# UWB___Sensor_Extension_Board.net
KiCad netlist of a schematic drawn in EasyEDA Pro
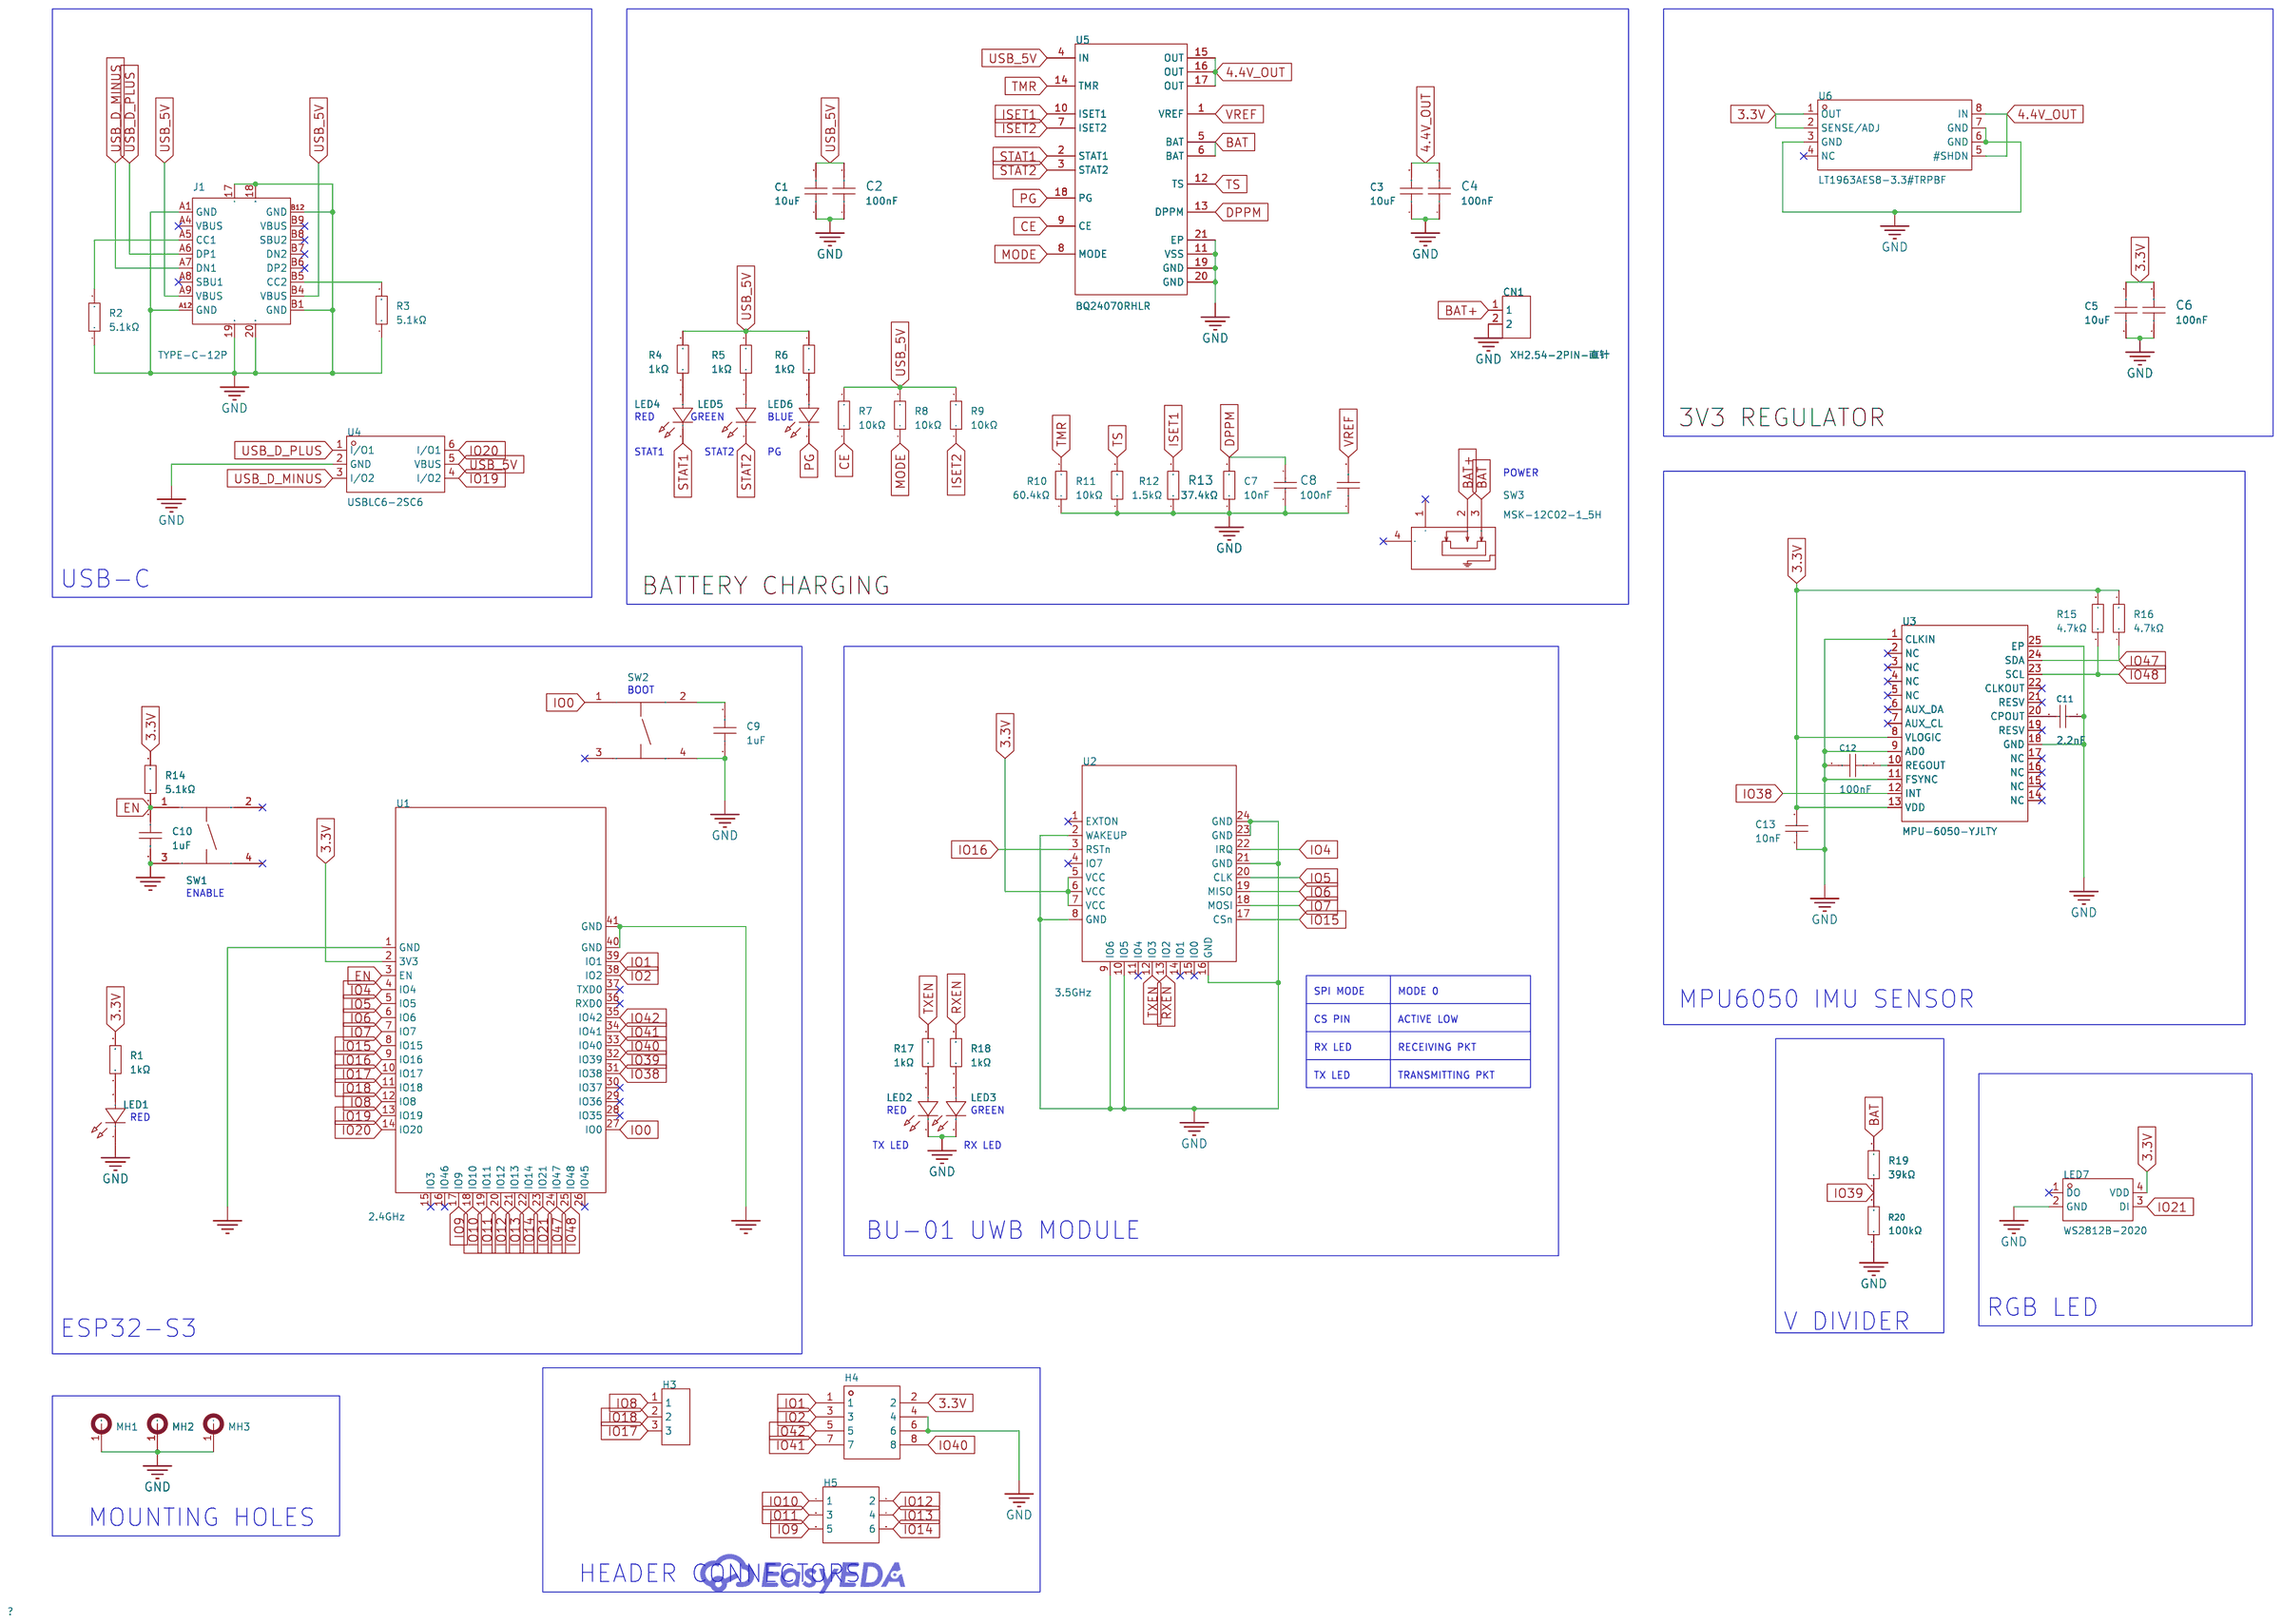
[diagram p0: schematic sheet]

(export (version "E")
  (design (tool "Eeschema 10.0.6"))
  (components
    (comp (ref "C1")
      (value "10uF")
      (footprint "easyedapro:C0603")
      (description "Capacitance:10uF Tolerance:±10% Tolerance:±10% Voltage Rating:10V Temperature Coefficient:X5R")
      (fields
        (field (name "Manufacturer Part") "CL10A106KP8NNNC")
        (field (name "Manufacturer") "SAMSUNG(三星)")
      )
      (libsource (lib "easyedapro") (part "CL10A106KP8NNNC"))
    )
    (comp (ref "C2")
      (value "100nF")
      (footprint "easyedapro:C0603")
      (description "Capacitance:100nF Tolerance:±10% Tolerance:±10% Voltage Rating:10V Temperature Coefficient:X7R")
      (fields
        (field (name "Manufacturer Part") "CC0603KRX7R6BB104")
        (field (name "Manufacturer") "YAGEO(国巨)")
      )
      (libsource (lib "easyedapro") (part "CC0603KRX7R6BB104"))
    )
    (comp (ref "C3")
      (value "10uF")
      (footprint "easyedapro:C0603")
      (description "Capacitance:10uF Tolerance:±10% Tolerance:±10% Voltage Rating:10V Temperature Coefficient:X5R")
      (fields
        (field (name "Manufacturer Part") "CL10A106KP8NNNC")
        (field (name "Manufacturer") "SAMSUNG(三星)")
      )
      (libsource (lib "easyedapro") (part "CL10A106KP8NNNC"))
    )
    (comp (ref "C4")
      (value "100nF")
      (footprint "easyedapro:C0603")
      (description "Capacitance:100nF Tolerance:±10% Tolerance:±10% Voltage Rating:10V Temperature Coefficient:X7R")
      (fields
        (field (name "Manufacturer Part") "CC0603KRX7R6BB104")
        (field (name "Manufacturer") "YAGEO(国巨)")
      )
      (libsource (lib "easyedapro") (part "CC0603KRX7R6BB104"))
    )
    (comp (ref "C5")
      (value "10uF")
      (footprint "easyedapro:C0603")
      (description "Capacitance:10uF Tolerance:±10% Tolerance:±10% Voltage Rating:10V Temperature Coefficient:X5R")
      (fields
        (field (name "Manufacturer Part") "CL10A106KP8NNNC")
        (field (name "Manufacturer") "SAMSUNG(三星)")
      )
      (libsource (lib "easyedapro") (part "CL10A106KP8NNNC"))
    )
    (comp (ref "C6")
      (value "100nF")
      (footprint "easyedapro:C0603")
      (description "Capacitance:100nF Tolerance:±10% Tolerance:±10% Voltage Rating:10V Temperature Coefficient:X7R")
      (fields
        (field (name "Manufacturer Part") "CC0603KRX7R6BB104")
        (field (name "Manufacturer") "YAGEO(国巨)")
      )
      (libsource (lib "easyedapro") (part "CC0603KRX7R6BB104"))
    )
    (comp (ref "C7")
      (value "10nF")
      (footprint "easyedapro:C0603")
      (description "Capacitance:10nF Tolerance:±5% Tolerance:±5% Voltage Rating:50V Temperature Coefficient:X7R")
      (fields
        (field (name "Manufacturer Part") "CC0603JRX7R9BB103")
        (field (name "Manufacturer") "YAGEO(国巨)")
      )
      (libsource (lib "easyedapro") (part "CC0603JRX7R9BB103"))
    )
    (comp (ref "C8")
      (value "100nF")
      (footprint "easyedapro:C0603")
      (description "Capacitance:100nF Tolerance:±10% Tolerance:±10% Voltage Rating:10V Temperature Coefficient:X7R")
      (fields
        (field (name "Manufacturer Part") "CC0603KRX7R6BB104")
        (field (name "Manufacturer") "YAGEO(国巨)")
      )
      (libsource (lib "easyedapro") (part "CC0603KRX7R6BB104"))
    )
    (comp (ref "C9")
      (value "1uF")
      (footprint "easyedapro:C0603")
      (fields (field (name "Manufacturer Part") "0603X105K250CT") (field (name "Manufacturer") "Walsin(华新科)"))
      (libsource (lib "easyedapro") (part "0603X105K250CT"))
    )
    (comp (ref "C10")
      (value "1uF")
      (footprint "easyedapro:C0603")
      (fields (field (name "Manufacturer Part") "0603X105K250CT") (field (name "Manufacturer") "Walsin(华新科)"))
      (libsource (lib "easyedapro") (part "0603X105K250CT"))
    )
    (comp (ref "C11")
      (value "2.2nF")
      (footprint "easyedapro:C0603")
      (description "Capacitance:2.2nF Tolerance:±5% Tolerance:±5% Voltage Rating:50V Temperature Coefficient:NP0")
      (fields
        (field (name "Manufacturer Part") "CC0603JRNPO9BN222")
        (field (name "Manufacturer") "YAGEO(国巨)")
      )
      (libsource (lib "easyedapro") (part "CC0603JRNPO9BN222"))
    )
    (comp (ref "C12")
      (value "100nF")
      (footprint "easyedapro:C0603")
      (description "Capacitance:100nF Tolerance:±10% Tolerance:±10% Voltage Rating:10V Temperature Coefficient:X7R")
      (fields
        (field (name "Manufacturer Part") "CC0603KRX7R6BB104")
        (field (name "Manufacturer") "YAGEO(国巨)")
      )
      (libsource (lib "easyedapro") (part "CC0603KRX7R6BB104"))
    )
    (comp (ref "C13")
      (value "10nF")
      (footprint "easyedapro:C0603")
      (description "Capacitance:10nF Tolerance:±5% Tolerance:±5% Voltage Rating:50V Temperature Coefficient:X7R")
      (fields
        (field (name "Manufacturer Part") "CC0603JRX7R9BB103")
        (field (name "Manufacturer") "YAGEO(国巨)")
      )
      (libsource (lib "easyedapro") (part "CC0603JRX7R9BB103"))
    )
    (comp (ref "CN1")
      (value "XH2.54-2PIN-直针")
      (footprint "easyedapro:CONN-TH_XH2.54-2P")
      (libsource (lib "easyedapro") (part "XH2.54-2PIN-直针"))
    )
    (comp (ref "H3")
      (value "~")
      (footprint "easyedapro:HDR-TH_3P-P2.54-V-M")
      (libsource (lib "easyedapro") (part "PZ254V-11-03P_C2937625"))
    )
    (comp (ref "H4")
      (value "~")
      (footprint "easyedapro:HDR-TH_8P-P2.54-V-M-R2-C4-S2.54")
      (libsource (lib "easyedapro") (part "HDR-M-2.54_2x4"))
    )
    (comp (ref "H5")
      (value "~")
      (footprint "easyedapro:HDR-TH_6P-P2.54-V-R2-C3-S2.54_A2541WV-2X3P")
      (libsource (lib "easyedapro") (part "HDR-M-2.54_2x3"))
    )
    (comp (ref "J1")
      (value "TYPE-C-12P")
      (footprint "easyedapro:USB-SMD_TYPE-C16PIN")
      (libsource (lib "easyedapro") (part "TYPE-C-12P"))
    )
    (comp (ref "LED1")
      (value "19-217/GHC-YR1S2/6T")
      (footprint "easyedapro:LED0603-RD_GREEN")
      (fields (field (name "Manufacturer") "EVERLIGHT(亿光)"))
      (libsource (lib "easyedapro") (part "19-217/GHC-YR1S2/6T"))
    )
    (comp (ref "LED2")
      (value "19-217/GHC-YR1S2/6T")
      (footprint "easyedapro:LED0603-RD_GREEN")
      (fields (field (name "Manufacturer") "EVERLIGHT(亿光)"))
      (libsource (lib "easyedapro") (part "19-217/GHC-YR1S2/6T"))
    )
    (comp (ref "LED3")
      (value "19-217/GHC-YR1S2/6T")
      (footprint "easyedapro:LED0603-RD_GREEN")
      (fields (field (name "Manufacturer") "EVERLIGHT(亿光)"))
      (libsource (lib "easyedapro") (part "19-217/GHC-YR1S2/6T"))
    )
    (comp (ref "LED4")
      (value "19-217/GHC-YR1S2/6T")
      (footprint "easyedapro:LED0603-RD_GREEN")
      (fields (field (name "Manufacturer") "EVERLIGHT(亿光)"))
      (libsource (lib "easyedapro") (part "19-217/GHC-YR1S2/6T"))
    )
    (comp (ref "LED5")
      (value "19-217/GHC-YR1S2/6T")
      (footprint "easyedapro:LED0603-RD_GREEN")
      (fields (field (name "Manufacturer") "EVERLIGHT(亿光)"))
      (libsource (lib "easyedapro") (part "19-217/GHC-YR1S2/6T"))
    )
    (comp (ref "LED6")
      (value "19-217/GHC-YR1S2/6T")
      (footprint "easyedapro:LED0603-RD_GREEN")
      (fields (field (name "Manufacturer") "EVERLIGHT(亿光)"))
      (libsource (lib "easyedapro") (part "19-217/GHC-YR1S2/6T"))
    )
    (comp (ref "LED7")
      (value "WS2812B-2020")
      (footprint "easyedapro:LED-SMD_4P-L2.0-W2.0-TL_WS2812B-2020")
      (fields (field (name "Manufacturer") "worldsemi"))
      (libsource (lib "easyedapro") (part "WS2812B-2020"))
    )
    (comp (ref "MH1")
      (value "~")
      (footprint "easyedapro:MH_7.5x2.7mm")
      (libsource (lib "easyedapro") (part "MH_7.5x2.7mm"))
    )
    (comp (ref "MH2")
      (value "~")
      (footprint "easyedapro:MH_7.5x2.7mm")
      (libsource (lib "easyedapro") (part "MH_7.5x2.7mm"))
    )
    (comp (ref "MH3")
      (value "~")
      (footprint "easyedapro:MH_7.5x2.7mm")
      (libsource (lib "easyedapro") (part "MH_7.5x2.7mm"))
    )
    (comp (ref "R1")
      (value "1kΩ")
      (footprint "easyedapro:R0603")
      (fields (field (name "Manufacturer Part") "RC0603FR-071KL") (field (name "Manufacturer") "YAGEO(国巨)"))
      (libsource (lib "easyedapro") (part "RC0603FR-071KL"))
    )
    (comp (ref "R2")
      (value "5.1kΩ")
      (footprint "easyedapro:R0603")
      (fields (field (name "Manufacturer Part") "RC0603FR-075K1L") (field (name "Manufacturer") "YAGEO(国巨)"))
      (libsource (lib "easyedapro") (part "RC0603FR-075K1L"))
    )
    (comp (ref "R3")
      (value "5.1kΩ")
      (footprint "easyedapro:R0603")
      (fields (field (name "Manufacturer Part") "RC0603FR-075K1L") (field (name "Manufacturer") "YAGEO(国巨)"))
      (libsource (lib "easyedapro") (part "RC0603FR-075K1L"))
    )
    (comp (ref "R4")
      (value "1kΩ")
      (footprint "easyedapro:R0603")
      (fields (field (name "Manufacturer Part") "RC0603FR-071KL") (field (name "Manufacturer") "YAGEO(国巨)"))
      (libsource (lib "easyedapro") (part "RC0603FR-071KL"))
    )
    (comp (ref "R5")
      (value "1kΩ")
      (footprint "easyedapro:R0603")
      (fields (field (name "Manufacturer Part") "RC0603FR-071KL") (field (name "Manufacturer") "YAGEO(国巨)"))
      (libsource (lib "easyedapro") (part "RC0603FR-071KL"))
    )
    (comp (ref "R6")
      (value "1kΩ")
      (footprint "easyedapro:R0603")
      (fields (field (name "Manufacturer Part") "RC0603FR-071KL") (field (name "Manufacturer") "YAGEO(国巨)"))
      (libsource (lib "easyedapro") (part "RC0603FR-071KL"))
    )
    (comp (ref "R7")
      (value "10kΩ")
      (footprint "easyedapro:R0603")
      (fields (field (name "Manufacturer Part") "RC0603FR-0710KL") (field (name "Manufacturer") "YAGEO(国巨)"))
      (libsource (lib "easyedapro") (part "RC0603FR-0710KL"))
    )
    (comp (ref "R8")
      (value "10kΩ")
      (footprint "easyedapro:R0603")
      (fields (field (name "Manufacturer Part") "RC0603FR-0710KL") (field (name "Manufacturer") "YAGEO(国巨)"))
      (libsource (lib "easyedapro") (part "RC0603FR-0710KL"))
    )
    (comp (ref "R9")
      (value "10kΩ")
      (footprint "easyedapro:R0603")
      (fields (field (name "Manufacturer Part") "RC0603FR-0710KL") (field (name "Manufacturer") "YAGEO(国巨)"))
      (libsource (lib "easyedapro") (part "RC0603FR-0710KL"))
    )
    (comp (ref "R10")
      (value "60.4kΩ")
      (footprint "easyedapro:R0603")
      (fields (field (name "Manufacturer Part") "RC0603FR-0760K4L") (field (name "Manufacturer") "YAGEO(国巨)"))
      (libsource (lib "easyedapro") (part "RC0603FR-0760K4L"))
    )
    (comp (ref "R11")
      (value "10kΩ")
      (footprint "easyedapro:R0603")
      (fields (field (name "Manufacturer Part") "RC0603FR-0710KL") (field (name "Manufacturer") "YAGEO(国巨)"))
      (libsource (lib "easyedapro") (part "RC0603FR-0710KL"))
    )
    (comp (ref "R12")
      (value "1.5kΩ")
      (footprint "easyedapro:R0603")
      (fields (field (name "Manufacturer Part") "RC0603FR-071K5L") (field (name "Manufacturer") "YAGEO(国巨)"))
      (libsource (lib "easyedapro") (part "RC0603FR-071K5L"))
    )
    (comp (ref "R13")
      (value "37.4kΩ")
      (footprint "easyedapro:R0603")
      (fields
        (field (name "Manufacturer Part") "0603WAF3742T5E")
        (field (name "Manufacturer") "UNI-ROYAL(厚声)")
      )
      (libsource (lib "easyedapro") (part "0603WAF3742T5E"))
    )
    (comp (ref "R14")
      (value "5.1kΩ")
      (footprint "easyedapro:R0603")
      (fields (field (name "Manufacturer Part") "RC0603FR-075K1L") (field (name "Manufacturer") "YAGEO(国巨)"))
      (libsource (lib "easyedapro") (part "RC0603FR-075K1L"))
    )
    (comp (ref "R15")
      (value "4.7kΩ")
      (footprint "easyedapro:R0603")
      (fields (field (name "Manufacturer Part") "RC0603FR-074K7L") (field (name "Manufacturer") "YAGEO(国巨)"))
      (libsource (lib "easyedapro") (part "RC0603FR-074K7L"))
    )
    (comp (ref "R16")
      (value "4.7kΩ")
      (footprint "easyedapro:R0603")
      (fields (field (name "Manufacturer Part") "RC0603FR-074K7L") (field (name "Manufacturer") "YAGEO(国巨)"))
      (libsource (lib "easyedapro") (part "RC0603FR-074K7L"))
    )
    (comp (ref "R17")
      (value "1kΩ")
      (footprint "easyedapro:R0603")
      (fields (field (name "Manufacturer Part") "RC0603FR-071KL") (field (name "Manufacturer") "YAGEO(国巨)"))
      (libsource (lib "easyedapro") (part "RC0603FR-071KL"))
    )
    (comp (ref "R18")
      (value "1kΩ")
      (footprint "easyedapro:R0603")
      (fields (field (name "Manufacturer Part") "RC0603FR-071KL") (field (name "Manufacturer") "YAGEO(国巨)"))
      (libsource (lib "easyedapro") (part "RC0603FR-071KL"))
    )
    (comp (ref "R19")
      (value "39kΩ")
      (footprint "easyedapro:R0603")
      (fields (field (name "Manufacturer Part") "RC0603FR-0739KL") (field (name "Manufacturer") "YAGEO(国巨)"))
      (libsource (lib "easyedapro") (part "RC0603FR-0739KL"))
    )
    (comp (ref "R20")
      (value "100kΩ")
      (footprint "easyedapro:R0603")
      (fields (field (name "Manufacturer Part") "RC0603FR-07100KL") (field (name "Manufacturer") "YAGEO(国巨)"))
      (libsource (lib "easyedapro") (part "RC0603FR-07100KL"))
    )
    (comp (ref "SW1")
      (value "TS3315A")
      (footprint "easyedapro:SW-SMD_4P-L3.4-W3.4-P2.00-LS4.0")
      (fields (field (name "Manufacturer") "SHOU HAN(首韩)"))
      (libsource (lib "easyedapro") (part "TS3315A"))
    )
    (comp (ref "SW2")
      (value "TS3315A")
      (footprint "easyedapro:SW-SMD_4P-L3.4-W3.4-P2.00-LS4.0")
      (fields (field (name "Manufacturer") "SHOU HAN(首韩)"))
      (libsource (lib "easyedapro") (part "TS3315A"))
    )
    (comp (ref "SW3")
      (value "MSK-12C02-1_5H")
      (footprint "easyedapro:SW-TH_MSK12C02")
      (libsource (lib "easyedapro") (part "MSK-12C02-1_5H"))
    )
    (comp (ref "U1")
      (value "2.4GHz")
      (footprint "easyedapro:WIRELM-SMD_ESP32-S3-WROOM-1")
      (fields
        (field (name "Manufacturer Part") "ESP32-S3-WROOM-1-N16R8")
        (field (name "Manufacturer") "ESPRESSIF(乐鑫)")
      )
      (libsource (lib "easyedapro") (part "ESP32-S3-WROOM-1(N16R8)"))
    )
    (comp (ref "U2")
      (value "3.5GHz")
      (footprint "easyedapro:COMM-SMD_BU01")
      (fields (field (name "Manufacturer Part") "BU01") (field (name "Manufacturer") "Ai-Thinker(安信可)"))
      (libsource (lib "easyedapro") (part "BU01"))
    )
    (comp (ref "U3")
      (value "MPU-6050-YJLTY")
      (footprint "easyedapro:QFN-24_L4.0-W4.0-P0.50-TL-EP2.7")
      (libsource (lib "easyedapro") (part "MPU-6050-YJLTY_C9900004367"))
    )
    (comp (ref "U4")
      (value "USBLC6-2SC6")
      (footprint "easyedapro:SOT-23-6_L2.9-W1.6-P0.95-LS2.8-BL")
      (description "Maximum Clamping Voltage:15V Breakdown Voltage:6V Number of Lines:双路 Type:ESD")
      (fields (field (name "Manufacturer") "UMW(友台半导体)"))
      (libsource (lib "easyedapro") (part "USBLC6-2SC6_C2687116"))
    )
    (comp (ref "U5")
      (value "BQ24070RHLR")
      (footprint "easyedapro:QFN-20_L4.7-W3.7-P0.50-BL-EP")
      (fields (field (name "Manufacturer") "TI(德州仪器)"))
      (libsource (lib "easyedapro") (part "BQ24070RHLR"))
    )
    (comp (ref "U6")
      (value "LT1963AES8-3.3#TRPBF")
      (footprint "easyedapro:SO-8_L4.9-W3.9-P1.27-LS5.9-BL")
      (description "Output Type:-")
      (libsource (lib "easyedapro") (part "LT1963AES8-3.3#TRPBF_C514417"))
    )
  )
  (nets
    (net (code "1") (name "3.3V") (class "Default")
      (node (ref "C13") (pin "2") (pinfunction "2_2") (pintype "input"))
      (node (ref "C5") (pin "2") (pinfunction "2_2") (pintype "unspecified"))
      (node (ref "C6") (pin "2") (pinfunction "2_2") (pintype "input"))
      (node (ref "H4") (pin "2") (pinfunction "2_2") (pintype "input"))
      (node (ref "LED7") (pin "4") (pinfunction "VDD_4") (pintype "unspecified"))
      (node (ref "R1") (pin "2") (pinfunction "2_2") (pintype "input"))
      (node (ref "R14") (pin "2") (pinfunction "2_2") (pintype "input"))
      (node (ref "R15") (pin "2") (pinfunction "2_2") (pintype "input"))
      (node (ref "R16") (pin "2") (pinfunction "2_2") (pintype "input"))
      (node (ref "U1") (pin "2") (pinfunction "3V3_2") (pintype "unspecified"))
      (node (ref "U2") (pin "5") (pinfunction "VCC_5") (pintype "unspecified"))
      (node (ref "U2") (pin "6") (pinfunction "VCC_6") (pintype "unspecified"))
      (node (ref "U2") (pin "7") (pinfunction "VCC_7") (pintype "unspecified"))
      (node (ref "U3") (pin "13") (pinfunction "VDD_13") (pintype "unspecified"))
      (node (ref "U3") (pin "8") (pinfunction "VLOGIC_8") (pintype "unspecified"))
      (node (ref "U6") (pin "1") (pinfunction "OUT_1") (pintype "unspecified"))
      (node (ref "U6") (pin "2") (pinfunction "SENSE/ADJ_2") (pintype "unspecified"))
    )
    (net (code "2") (name "4.4V_OUT") (class "Default")
      (node (ref "C3") (pin "2") (pinfunction "2_2") (pintype "unspecified"))
      (node (ref "C4") (pin "2") (pinfunction "2_2") (pintype "input"))
      (node (ref "U5") (pin "15") (pinfunction "OUT_15") (pintype "unspecified"))
      (node (ref "U5") (pin "16") (pinfunction "OUT_16") (pintype "unspecified"))
      (node (ref "U5") (pin "17") (pinfunction "OUT_17") (pintype "unspecified"))
      (node (ref "U6") (pin "5") (pinfunction "#SHDN_5") (pintype "unspecified"))
      (node (ref "U6") (pin "8") (pinfunction "IN_8") (pintype "unspecified"))
    )
    (net (code "3") (name "BAT") (class "Default")
      (node (ref "R19") (pin "2") (pinfunction "2_2") (pintype "unspecified"))
      (node (ref "SW3") (pin "3") (pinfunction "3_3") (pintype "unspecified"))
      (node (ref "U5") (pin "5") (pinfunction "BAT_5") (pintype "unspecified"))
      (node (ref "U5") (pin "6") (pinfunction "BAT_6") (pintype "unspecified"))
    )
    (net (code "4") (name "BAT+") (class "Default")
      (node (ref "CN1") (pin "1") (pinfunction "1_1") (pintype "unspecified"))
      (node (ref "SW3") (pin "2") (pinfunction "2_2") (pintype "unspecified"))
    )
    (net (code "5") (name "CE") (class "Default")
      (node (ref "R7") (pin "1") (pinfunction "1_1") (pintype "input"))
      (node (ref "U5") (pin "9") (pinfunction "CE_9") (pintype "unspecified"))
    )
    (net (code "6") (name "DPPM") (class "Default")
      (node (ref "C7") (pin "2") (pinfunction "2_2") (pintype "input"))
      (node (ref "R13") (pin "2") (pinfunction "2_2") (pintype "input"))
      (node (ref "U5") (pin "13") (pinfunction "DPPM_13") (pintype "unspecified"))
    )
    (net (code "7") (name "EN") (class "Default")
      (node (ref "C10") (pin "1") (pinfunction "1_1") (pintype "unspecified"))
      (node (ref "R14") (pin "1") (pinfunction "1_1") (pintype "input"))
      (node (ref "SW1") (pin "1") (pinfunction "A_1") (pintype "unspecified"))
      (node (ref "U1") (pin "3") (pinfunction "EN_3") (pintype "unspecified"))
    )
    (net (code "8") (name "GND") (class "Default")
      (node (ref "C1") (pin "1") (pinfunction "1_1") (pintype "unspecified"))
      (node (ref "C10") (pin "2") (pinfunction "2_2") (pintype "unspecified"))
      (node (ref "C11") (pin "2") (pinfunction "2_2") (pintype "input"))
      (node (ref "C12") (pin "2") (pinfunction "2_2") (pintype "input"))
      (node (ref "C13") (pin "1") (pinfunction "1_1") (pintype "input"))
      (node (ref "C2") (pin "1") (pinfunction "1_1") (pintype "input"))
      (node (ref "C3") (pin "1") (pinfunction "1_1") (pintype "unspecified"))
      (node (ref "C4") (pin "1") (pinfunction "1_1") (pintype "input"))
      (node (ref "C5") (pin "1") (pinfunction "1_1") (pintype "unspecified"))
      (node (ref "C6") (pin "1") (pinfunction "1_1") (pintype "input"))
      (node (ref "C7") (pin "1") (pinfunction "1_1") (pintype "input"))
      (node (ref "C8") (pin "1") (pinfunction "1_1") (pintype "input"))
      (node (ref "C9") (pin "2") (pinfunction "2_2") (pintype "unspecified"))
      (node (ref "CN1") (pin "2") (pinfunction "2_2") (pintype "unspecified"))
      (node (ref "H4") (pin "4") (pinfunction "4_4") (pintype "input"))
      (node (ref "H4") (pin "6") (pinfunction "6_6") (pintype "input"))
      (node (ref "J1") (pin "17") (pinfunction "17_17") (pintype "unspecified"))
      (node (ref "J1") (pin "18") (pinfunction "18_18") (pintype "unspecified"))
      (node (ref "J1") (pin "19") (pinfunction "19_19") (pintype "unspecified"))
      (node (ref "J1") (pin "20") (pinfunction "20_20") (pintype "unspecified"))
      (node (ref "J1") (pin "A1") (pinfunction "GND_A1") (pintype "unspecified"))
      (node (ref "J1") (pin "A12") (pinfunction "GND_A12") (pintype "unspecified"))
      (node (ref "J1") (pin "B1") (pinfunction "GND_B1") (pintype "unspecified"))
      (node (ref "J1") (pin "B12") (pinfunction "GND_B12") (pintype "unspecified"))
      (node (ref "LED1") (pin "1") (pinfunction "K_1") (pintype "unspecified"))
      (node (ref "LED2") (pin "1") (pinfunction "K_1") (pintype "unspecified"))
      (node (ref "LED3") (pin "1") (pinfunction "K_1") (pintype "unspecified"))
      (node (ref "LED7") (pin "2") (pinfunction "GND_2") (pintype "unspecified"))
      (node (ref "MH1") (pin "1") (pinfunction "1_1") (pintype "input"))
      (node (ref "MH2") (pin "1") (pinfunction "1_1") (pintype "input"))
      (node (ref "MH3") (pin "1") (pinfunction "1_1") (pintype "input"))
      (node (ref "R10") (pin "1") (pinfunction "1_1") (pintype "unspecified"))
      (node (ref "R11") (pin "1") (pinfunction "1_1") (pintype "input"))
      (node (ref "R12") (pin "1") (pinfunction "1_1") (pintype "input"))
      (node (ref "R13") (pin "1") (pinfunction "1_1") (pintype "input"))
      (node (ref "R2") (pin "1") (pinfunction "1_1") (pintype "input"))
      (node (ref "R20") (pin "1") (pinfunction "1_1") (pintype "input"))
      (node (ref "R3") (pin "1") (pinfunction "1_1") (pintype "input"))
      (node (ref "SW1") (pin "3") (pinfunction "C_3") (pintype "unspecified"))
      (node (ref "SW2") (pin "4") (pinfunction "D_4") (pintype "unspecified"))
      (node (ref "U1") (pin "1") (pinfunction "GND_1") (pintype "unspecified"))
      (node (ref "U1") (pin "40") (pinfunction "GND_40") (pintype "unspecified"))
      (node (ref "U1") (pin "41") (pinfunction "GND_41") (pintype "unspecified"))
      (node (ref "U2") (pin "10") (pinfunction "IO5_10") (pintype "unspecified"))
      (node (ref "U2") (pin "16") (pinfunction "GND_16") (pintype "unspecified"))
      (node (ref "U2") (pin "2") (pinfunction "WAKEUP_2") (pintype "unspecified"))
      (node (ref "U2") (pin "21") (pinfunction "GND_21") (pintype "unspecified"))
      (node (ref "U2") (pin "23") (pinfunction "GND_23") (pintype "unspecified"))
      (node (ref "U2") (pin "24") (pinfunction "GND_24") (pintype "unspecified"))
      (node (ref "U2") (pin "8") (pinfunction "GND_8") (pintype "unspecified"))
      (node (ref "U2") (pin "9") (pinfunction "IO6_9") (pintype "unspecified"))
      (node (ref "U3") (pin "1") (pinfunction "CLKIN_1") (pintype "unspecified"))
      (node (ref "U3") (pin "11") (pinfunction "FSYNC_11") (pintype "unspecified"))
      (node (ref "U3") (pin "18") (pinfunction "GND_18") (pintype "unspecified"))
      (node (ref "U3") (pin "25") (pinfunction "EP_25") (pintype "unspecified"))
      (node (ref "U3") (pin "9") (pinfunction "AD0_9") (pintype "unspecified"))
      (node (ref "U4") (pin "2") (pinfunction "GND_2") (pintype "unspecified"))
      (node (ref "U5") (pin "11") (pinfunction "VSS_11") (pintype "unspecified"))
      (node (ref "U5") (pin "19") (pinfunction "GND_19") (pintype "unspecified"))
      (node (ref "U5") (pin "20") (pinfunction "GND_20") (pintype "unspecified"))
      (node (ref "U5") (pin "21") (pinfunction "EP_21") (pintype "unspecified"))
      (node (ref "U6") (pin "3") (pinfunction "GND_3") (pintype "unspecified"))
      (node (ref "U6") (pin "6") (pinfunction "GND_6") (pintype "unspecified"))
      (node (ref "U6") (pin "7") (pinfunction "GND_7") (pintype "unspecified"))
    )
    (net (code "9") (name "IO0") (class "Default")
      (node (ref "SW2") (pin "1") (pinfunction "A_1") (pintype "unspecified"))
      (node (ref "U1") (pin "27") (pinfunction "IO0_27") (pintype "unspecified"))
    )
    (net (code "10") (name "IO1") (class "Default")
      (node (ref "H4") (pin "1") (pinfunction "1_1") (pintype "input"))
      (node (ref "U1") (pin "39") (pinfunction "IO1_39") (pintype "unspecified"))
    )
    (net (code "11") (name "IO2") (class "Default")
      (node (ref "H4") (pin "3") (pinfunction "3_3") (pintype "input"))
      (node (ref "U1") (pin "38") (pinfunction "IO2_38") (pintype "unspecified"))
    )
    (net (code "12") (name "IO4") (class "Default")
      (node (ref "U1") (pin "4") (pinfunction "IO4_4") (pintype "unspecified"))
      (node (ref "U2") (pin "22") (pinfunction "IRQ_22") (pintype "unspecified"))
    )
    (net (code "13") (name "IO5") (class "Default")
      (node (ref "U1") (pin "5") (pinfunction "IO5_5") (pintype "unspecified"))
      (node (ref "U2") (pin "20") (pinfunction "CLK_20") (pintype "unspecified"))
    )
    (net (code "14") (name "IO6") (class "Default")
      (node (ref "U1") (pin "6") (pinfunction "IO6_6") (pintype "unspecified"))
      (node (ref "U2") (pin "19") (pinfunction "MISO_19") (pintype "unspecified"))
    )
    (net (code "15") (name "IO7") (class "Default")
      (node (ref "U1") (pin "7") (pinfunction "IO7_7") (pintype "unspecified"))
      (node (ref "U2") (pin "18") (pinfunction "MOSI_18") (pintype "unspecified"))
    )
    (net (code "16") (name "IO8") (class "Default")
      (node (ref "H3") (pin "1") (pinfunction "1_1") (pintype "unspecified"))
      (node (ref "U1") (pin "12") (pinfunction "IO8_12") (pintype "unspecified"))
    )
    (net (code "17") (name "IO9") (class "Default")
      (node (ref "H5") (pin "5") (pinfunction "5_5") (pintype "input"))
      (node (ref "U1") (pin "17") (pinfunction "IO9_17") (pintype "unspecified"))
    )
    (net (code "18") (name "IO10") (class "Default")
      (node (ref "H5") (pin "1") (pinfunction "1_1") (pintype "input"))
      (node (ref "U1") (pin "18") (pinfunction "IO10_18") (pintype "unspecified"))
    )
    (net (code "19") (name "IO11") (class "Default")
      (node (ref "H5") (pin "3") (pinfunction "3_3") (pintype "input"))
      (node (ref "U1") (pin "19") (pinfunction "IO11_19") (pintype "unspecified"))
    )
    (net (code "20") (name "IO12") (class "Default")
      (node (ref "H5") (pin "2") (pinfunction "2_2") (pintype "input"))
      (node (ref "U1") (pin "20") (pinfunction "IO12_20") (pintype "unspecified"))
    )
    (net (code "21") (name "IO13") (class "Default")
      (node (ref "H5") (pin "4") (pinfunction "4_4") (pintype "input"))
      (node (ref "U1") (pin "21") (pinfunction "IO13_21") (pintype "unspecified"))
    )
    (net (code "22") (name "IO14") (class "Default")
      (node (ref "H5") (pin "6") (pinfunction "6_6") (pintype "input"))
      (node (ref "U1") (pin "22") (pinfunction "IO14_22") (pintype "unspecified"))
    )
    (net (code "23") (name "IO15") (class "Default")
      (node (ref "U1") (pin "8") (pinfunction "IO15_8") (pintype "unspecified"))
      (node (ref "U2") (pin "17") (pinfunction "CSn_17") (pintype "unspecified"))
    )
    (net (code "24") (name "IO16") (class "Default")
      (node (ref "U1") (pin "9") (pinfunction "IO16_9") (pintype "unspecified"))
      (node (ref "U2") (pin "3") (pinfunction "RSTn_3") (pintype "unspecified"))
    )
    (net (code "25") (name "IO17") (class "Default")
      (node (ref "H3") (pin "3") (pinfunction "3_3") (pintype "unspecified"))
      (node (ref "U1") (pin "10") (pinfunction "IO17_10") (pintype "unspecified"))
    )
    (net (code "26") (name "IO18") (class "Default")
      (node (ref "H3") (pin "2") (pinfunction "2_2") (pintype "unspecified"))
      (node (ref "U1") (pin "11") (pinfunction "IO18_11") (pintype "unspecified"))
    )
    (net (code "27") (name "IO19") (class "Default")
      (node (ref "U1") (pin "13") (pinfunction "IO19_13") (pintype "unspecified"))
      (node (ref "U4") (pin "4") (pinfunction "I/O2_4") (pintype "unspecified"))
    )
    (net (code "28") (name "IO20") (class "Default")
      (node (ref "U1") (pin "14") (pinfunction "IO20_14") (pintype "unspecified"))
      (node (ref "U4") (pin "6") (pinfunction "I/O1_6") (pintype "unspecified"))
    )
    (net (code "29") (name "IO21") (class "Default")
      (node (ref "LED7") (pin "3") (pinfunction "DI_3") (pintype "unspecified"))
      (node (ref "U1") (pin "23") (pinfunction "IO21_23") (pintype "unspecified"))
    )
    (net (code "30") (name "IO38") (class "Default")
      (node (ref "U1") (pin "31") (pinfunction "IO38_31") (pintype "unspecified"))
      (node (ref "U3") (pin "12") (pinfunction "INT_12") (pintype "unspecified"))
    )
    (net (code "31") (name "IO39") (class "Default")
      (node (ref "R19") (pin "1") (pinfunction "1_1") (pintype "unspecified"))
      (node (ref "R20") (pin "2") (pinfunction "2_2") (pintype "input"))
      (node (ref "U1") (pin "32") (pinfunction "IO39_32") (pintype "unspecified"))
    )
    (net (code "32") (name "IO40") (class "Default")
      (node (ref "H4") (pin "8") (pinfunction "8_8") (pintype "input"))
      (node (ref "U1") (pin "33") (pinfunction "IO40_33") (pintype "unspecified"))
    )
    (net (code "33") (name "IO41") (class "Default")
      (node (ref "H4") (pin "7") (pinfunction "7_7") (pintype "input"))
      (node (ref "U1") (pin "34") (pinfunction "IO41_34") (pintype "unspecified"))
    )
    (net (code "34") (name "IO42") (class "Default")
      (node (ref "H4") (pin "5") (pinfunction "5_5") (pintype "input"))
      (node (ref "U1") (pin "35") (pinfunction "IO42_35") (pintype "unspecified"))
    )
    (net (code "35") (name "IO47") (class "Default")
      (node (ref "R16") (pin "1") (pinfunction "1_1") (pintype "input"))
      (node (ref "U1") (pin "24") (pinfunction "IO47_24") (pintype "unspecified"))
      (node (ref "U3") (pin "24") (pinfunction "SDA_24") (pintype "unspecified"))
    )
    (net (code "36") (name "IO48") (class "Default")
      (node (ref "R15") (pin "1") (pinfunction "1_1") (pintype "input"))
      (node (ref "U1") (pin "25") (pinfunction "IO48_25") (pintype "unspecified"))
      (node (ref "U3") (pin "23") (pinfunction "SCL_23") (pintype "unspecified"))
    )
    (net (code "37") (name "ISET1") (class "Default")
      (node (ref "R12") (pin "2") (pinfunction "2_2") (pintype "input"))
      (node (ref "U5") (pin "10") (pinfunction "ISET1_10") (pintype "unspecified"))
    )
    (net (code "38") (name "ISET2") (class "Default")
      (node (ref "R9") (pin "1") (pinfunction "1_1") (pintype "input"))
      (node (ref "U5") (pin "7") (pinfunction "ISET2_7") (pintype "unspecified"))
    )
    (net (code "39") (name "MODE") (class "Default")
      (node (ref "R8") (pin "1") (pinfunction "1_1") (pintype "input"))
      (node (ref "U5") (pin "8") (pinfunction "MODE_8") (pintype "unspecified"))
    )
    (net (code "40") (name "Net-(J1-CC1)") (class "Default")
      (node (ref "J1") (pin "A5") (pinfunction "CC1_A5") (pintype "unspecified"))
      (node (ref "R2") (pin "2") (pinfunction "2_2") (pintype "input"))
    )
    (net (code "41") (name "Net-(J1-CC2)") (class "Default")
      (node (ref "J1") (pin "B5") (pinfunction "CC2_B5") (pintype "unspecified"))
      (node (ref "R3") (pin "2") (pinfunction "2_2") (pintype "input"))
    )
    (net (code "42") (name "Net-(LED1-A)") (class "Default")
      (node (ref "LED1") (pin "2") (pinfunction "A_2") (pintype "unspecified"))
      (node (ref "R1") (pin "1") (pinfunction "1_1") (pintype "input"))
    )
    (net (code "43") (name "Net-(LED2-A)") (class "Default")
      (node (ref "LED2") (pin "2") (pinfunction "A_2") (pintype "unspecified"))
      (node (ref "R17") (pin "1") (pinfunction "1_1") (pintype "input"))
    )
    (net (code "44") (name "Net-(LED3-A)") (class "Default")
      (node (ref "LED3") (pin "2") (pinfunction "A_2") (pintype "unspecified"))
      (node (ref "R18") (pin "1") (pinfunction "1_1") (pintype "input"))
    )
    (net (code "45") (name "Net-(LED4-A)") (class "Default")
      (node (ref "LED4") (pin "2") (pinfunction "A_2") (pintype "unspecified"))
      (node (ref "R4") (pin "1") (pinfunction "1_1") (pintype "input"))
    )
    (net (code "46") (name "Net-(LED5-A)") (class "Default")
      (node (ref "LED5") (pin "2") (pinfunction "A_2") (pintype "unspecified"))
      (node (ref "R5") (pin "1") (pinfunction "1_1") (pintype "input"))
    )
    (net (code "47") (name "Net-(LED6-A)") (class "Default")
      (node (ref "LED6") (pin "2") (pinfunction "A_2") (pintype "unspecified"))
      (node (ref "R6") (pin "1") (pinfunction "1_1") (pintype "input"))
    )
    (net (code "48") (name "Net-(SW2-B)") (class "Default")
      (node (ref "C9") (pin "1") (pinfunction "1_1") (pintype "unspecified"))
      (node (ref "SW2") (pin "2") (pinfunction "B_2") (pintype "unspecified"))
    )
    (net (code "49") (name "Net-(U3-CPOUT)") (class "Default")
      (node (ref "C11") (pin "1") (pinfunction "1_1") (pintype "input"))
      (node (ref "U3") (pin "20") (pinfunction "CPOUT_20") (pintype "unspecified"))
    )
    (net (code "50") (name "Net-(U3-REGOUT)") (class "Default")
      (node (ref "C12") (pin "1") (pinfunction "1_1") (pintype "input"))
      (node (ref "U3") (pin "10") (pinfunction "REGOUT_10") (pintype "unspecified"))
    )
    (net (code "51") (name "PG") (class "Default")
      (node (ref "LED6") (pin "1") (pinfunction "K_1") (pintype "unspecified"))
      (node (ref "U5") (pin "18") (pinfunction "PG_18") (pintype "unspecified"))
    )
    (net (code "52") (name "RXEN") (class "Default")
      (node (ref "R18") (pin "2") (pinfunction "2_2") (pintype "input"))
      (node (ref "U2") (pin "13") (pinfunction "IO2_13") (pintype "unspecified"))
    )
    (net (code "53") (name "STAT1") (class "Default")
      (node (ref "LED4") (pin "1") (pinfunction "K_1") (pintype "unspecified"))
      (node (ref "U5") (pin "2") (pinfunction "STAT1_2") (pintype "unspecified"))
    )
    (net (code "54") (name "STAT2") (class "Default")
      (node (ref "LED5") (pin "1") (pinfunction "K_1") (pintype "unspecified"))
      (node (ref "U5") (pin "3") (pinfunction "STAT2_3") (pintype "unspecified"))
    )
    (net (code "55") (name "TMR") (class "Default")
      (node (ref "R10") (pin "2") (pinfunction "2_2") (pintype "unspecified"))
      (node (ref "U5") (pin "14") (pinfunction "TMR_14") (pintype "unspecified"))
    )
    (net (code "56") (name "TS") (class "Default")
      (node (ref "R11") (pin "2") (pinfunction "2_2") (pintype "input"))
      (node (ref "U5") (pin "12") (pinfunction "TS_12") (pintype "unspecified"))
    )
    (net (code "57") (name "TXEN") (class "Default")
      (node (ref "R17") (pin "2") (pinfunction "2_2") (pintype "input"))
      (node (ref "U2") (pin "12") (pinfunction "IO3_12") (pintype "unspecified"))
    )
    (net (code "58") (name "USB_5V") (class "Default")
      (node (ref "C1") (pin "2") (pinfunction "2_2") (pintype "unspecified"))
      (node (ref "C2") (pin "2") (pinfunction "2_2") (pintype "input"))
      (node (ref "J1") (pin "A9") (pinfunction "VBUS_A9") (pintype "unspecified"))
      (node (ref "J1") (pin "B4") (pinfunction "VBUS_B4") (pintype "unspecified"))
      (node (ref "R4") (pin "2") (pinfunction "2_2") (pintype "input"))
      (node (ref "R5") (pin "2") (pinfunction "2_2") (pintype "input"))
      (node (ref "R6") (pin "2") (pinfunction "2_2") (pintype "input"))
      (node (ref "R7") (pin "2") (pinfunction "2_2") (pintype "input"))
      (node (ref "R8") (pin "2") (pinfunction "2_2") (pintype "input"))
      (node (ref "R9") (pin "2") (pinfunction "2_2") (pintype "input"))
      (node (ref "U4") (pin "5") (pinfunction "VBUS_5") (pintype "unspecified"))
      (node (ref "U5") (pin "4") (pinfunction "IN_4") (pintype "unspecified"))
    )
    (net (code "59") (name "USB_D_MINUS") (class "Default")
      (node (ref "J1") (pin "A7") (pinfunction "DN1_A7") (pintype "unspecified"))
      (node (ref "U4") (pin "3") (pinfunction "I/O2_3") (pintype "unspecified"))
    )
    (net (code "60") (name "USB_D_PLUS") (class "Default")
      (node (ref "J1") (pin "A6") (pinfunction "DP1_A6") (pintype "unspecified"))
      (node (ref "U4") (pin "1") (pinfunction "I/O1_1") (pintype "unspecified"))
    )
    (net (code "61") (name "VREF") (class "Default")
      (node (ref "C8") (pin "2") (pinfunction "2_2") (pintype "input"))
      (node (ref "U5") (pin "1") (pinfunction "VREF_1") (pintype "output"))
    )
    (net (code "62") (name "unconnected-(J1-DN2-PadB7)") (class "Default")
      (node (ref "J1") (pin "B7") (pinfunction "DN2_B7") (pintype "unspecified+no_connect"))
    )
    (net (code "63") (name "unconnected-(J1-DP2-PadB6)") (class "Default")
      (node (ref "J1") (pin "B6") (pinfunction "DP2_B6") (pintype "unspecified+no_connect"))
    )
    (net (code "64") (name "unconnected-(J1-SBU1-PadA8)") (class "Default")
      (node (ref "J1") (pin "A8") (pinfunction "SBU1_A8") (pintype "unspecified+no_connect"))
    )
    (net (code "65") (name "unconnected-(J1-SBU2-PadB8)") (class "Default")
      (node (ref "J1") (pin "B8") (pinfunction "SBU2_B8") (pintype "unspecified+no_connect"))
    )
    (net (code "66") (name "unconnected-(J1-VBUS-PadA4)") (class "Default")
      (node (ref "J1") (pin "A4") (pinfunction "VBUS_A4") (pintype "unspecified+no_connect"))
    )
    (net (code "67") (name "unconnected-(J1-VBUS-PadB9)") (class "Default")
      (node (ref "J1") (pin "B9") (pinfunction "VBUS_B9") (pintype "unspecified+no_connect"))
    )
    (net (code "68") (name "unconnected-(LED7-DO-Pad1)") (class "Default")
      (node (ref "LED7") (pin "1") (pinfunction "DO_1") (pintype "unspecified+no_connect"))
    )
    (net (code "69") (name "unconnected-(SW1-B-Pad2)") (class "Default")
      (node (ref "SW1") (pin "2") (pinfunction "B_2") (pintype "unspecified+no_connect"))
    )
    (net (code "70") (name "unconnected-(SW1-D-Pad4)") (class "Default")
      (node (ref "SW1") (pin "4") (pinfunction "D_4") (pintype "unspecified+no_connect"))
    )
    (net (code "71") (name "unconnected-(SW2-C-Pad3)") (class "Default")
      (node (ref "SW2") (pin "3") (pinfunction "C_3") (pintype "unspecified+no_connect"))
    )
    (net (code "72") (name "unconnected-(SW3-Pad1)") (class "Default")
      (node (ref "SW3") (pin "1") (pinfunction "1_1") (pintype "unspecified+no_connect"))
    )
    (net (code "73") (name "unconnected-(SW3-Pad4)") (class "Default")
      (node (ref "SW3") (pin "4") (pinfunction "4_4") (pintype "unspecified+no_connect"))
    )
    (net (code "74") (name "unconnected-(U1-IO3-Pad15)") (class "Default")
      (node (ref "U1") (pin "15") (pinfunction "IO3_15") (pintype "unspecified+no_connect"))
    )
    (net (code "75") (name "unconnected-(U1-IO35-Pad28)") (class "Default")
      (node (ref "U1") (pin "28") (pinfunction "IO35_28") (pintype "unspecified+no_connect"))
    )
    (net (code "76") (name "unconnected-(U1-IO36-Pad29)") (class "Default")
      (node (ref "U1") (pin "29") (pinfunction "IO36_29") (pintype "unspecified+no_connect"))
    )
    (net (code "77") (name "unconnected-(U1-IO37-Pad30)") (class "Default")
      (node (ref "U1") (pin "30") (pinfunction "IO37_30") (pintype "unspecified+no_connect"))
    )
    (net (code "78") (name "unconnected-(U1-IO45-Pad26)") (class "Default")
      (node (ref "U1") (pin "26") (pinfunction "IO45_26") (pintype "unspecified+no_connect"))
    )
    (net (code "79") (name "unconnected-(U1-IO46-Pad16)") (class "Default")
      (node (ref "U1") (pin "16") (pinfunction "IO46_16") (pintype "unspecified+no_connect"))
    )
    (net (code "80") (name "unconnected-(U1-RXD0-Pad36)") (class "Default")
      (node (ref "U1") (pin "36") (pinfunction "RXD0_36") (pintype "unspecified+no_connect"))
    )
    (net (code "81") (name "unconnected-(U1-TXD0-Pad37)") (class "Default")
      (node (ref "U1") (pin "37") (pinfunction "TXD0_37") (pintype "unspecified+no_connect"))
    )
    (net (code "82") (name "unconnected-(U2-EXTON-Pad1)") (class "Default")
      (node (ref "U2") (pin "1") (pinfunction "EXTON_1") (pintype "unspecified+no_connect"))
    )
    (net (code "83") (name "unconnected-(U2-IO0-Pad15)") (class "Default")
      (node (ref "U2") (pin "15") (pinfunction "IO0_15") (pintype "unspecified+no_connect"))
    )
    (net (code "84") (name "unconnected-(U2-IO1-Pad14)") (class "Default")
      (node (ref "U2") (pin "14") (pinfunction "IO1_14") (pintype "unspecified+no_connect"))
    )
    (net (code "85") (name "unconnected-(U2-IO4-Pad11)") (class "Default")
      (node (ref "U2") (pin "11") (pinfunction "IO4_11") (pintype "unspecified+no_connect"))
    )
    (net (code "86") (name "unconnected-(U2-IO7-Pad4)") (class "Default")
      (node (ref "U2") (pin "4") (pinfunction "IO7_4") (pintype "unspecified+no_connect"))
    )
    (net (code "87") (name "unconnected-(U3-AUX_CL-Pad7)") (class "Default")
      (node (ref "U3") (pin "7") (pinfunction "AUX_CL_7") (pintype "unspecified+no_connect"))
    )
    (net (code "88") (name "unconnected-(U3-AUX_DA-Pad6)") (class "Default")
      (node (ref "U3") (pin "6") (pinfunction "AUX_DA_6") (pintype "unspecified+no_connect"))
    )
    (net (code "89") (name "unconnected-(U3-CLKOUT-Pad22)") (class "Default")
      (node (ref "U3") (pin "22") (pinfunction "CLKOUT_22") (pintype "unspecified+no_connect"))
    )
    (net (code "90") (name "unconnected-(U3-NC-Pad2)") (class "Default")
      (node (ref "U3") (pin "2") (pinfunction "NC_2") (pintype "unspecified+no_connect"))
    )
    (net (code "91") (name "unconnected-(U3-NC-Pad3)") (class "Default")
      (node (ref "U3") (pin "3") (pinfunction "NC_3") (pintype "unspecified+no_connect"))
    )
    (net (code "92") (name "unconnected-(U3-NC-Pad4)") (class "Default")
      (node (ref "U3") (pin "4") (pinfunction "NC_4") (pintype "unspecified+no_connect"))
    )
    (net (code "93") (name "unconnected-(U3-NC-Pad5)") (class "Default")
      (node (ref "U3") (pin "5") (pinfunction "NC_5") (pintype "unspecified+no_connect"))
    )
    (net (code "94") (name "unconnected-(U3-NC-Pad14)") (class "Default")
      (node (ref "U3") (pin "14") (pinfunction "NC_14") (pintype "unspecified+no_connect"))
    )
    (net (code "95") (name "unconnected-(U3-NC-Pad15)") (class "Default")
      (node (ref "U3") (pin "15") (pinfunction "NC_15") (pintype "unspecified+no_connect"))
    )
    (net (code "96") (name "unconnected-(U3-NC-Pad16)") (class "Default")
      (node (ref "U3") (pin "16") (pinfunction "NC_16") (pintype "unspecified+no_connect"))
    )
    (net (code "97") (name "unconnected-(U3-NC-Pad17)") (class "Default")
      (node (ref "U3") (pin "17") (pinfunction "NC_17") (pintype "unspecified+no_connect"))
    )
    (net (code "98") (name "unconnected-(U3-RESV-Pad19)") (class "Default")
      (node (ref "U3") (pin "19") (pinfunction "RESV_19") (pintype "unspecified+no_connect"))
    )
    (net (code "99") (name "unconnected-(U3-RESV-Pad21)") (class "Default")
      (node (ref "U3") (pin "21") (pinfunction "RESV_21") (pintype "unspecified+no_connect"))
    )
    (net (code "100") (name "unconnected-(U6-NC-Pad4)") (class "Default")
      (node (ref "U6") (pin "4") (pinfunction "NC_4") (pintype "unspecified+no_connect"))
    )
  )
)
